# PW1555.net
KiCad netlist of a schematic drawn in Altium Designer
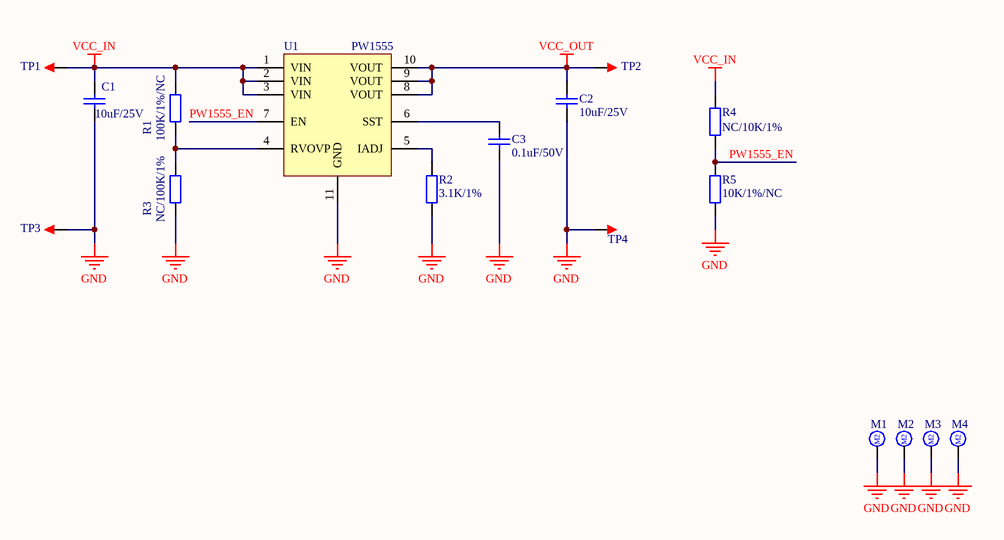
[diagram p0: PW1555.SchDoc]

(export (version "E")
  (design (tool "Eeschema 10.0.6"))
  (components
    (comp (ref "C1")
      (value "10uF/25V")
      (footprint "C0805_L")
      (description "贴片电容")
      (libsource (lib "0.1 - 电阻-电容-电感-晶振-晶体-磁珠-电位器") (part "C"))
    )
    (comp (ref "C2")
      (value "10uF/25V")
      (footprint "C0805_L")
      (description "贴片电容")
      (libsource (lib "0.1 - 电阻-电容-电感-晶振-晶体-磁珠-电位器") (part "C"))
    )
    (comp (ref "C3")
      (value "0.1uF/50V")
      (footprint "C0402_L")
      (description "贴片电容")
      (libsource (lib "0.1 - 电阻-电容-电感-晶振-晶体-磁珠-电位器") (part "C"))
    )
    (comp (ref "M1")
      (value "M2")
      (footprint "M2焊盘")
      (description "M2孔支撑柱")
      (libsource (lib "USER_Lib") (part "M2系列"))
    )
    (comp (ref "M2")
      (value "M2")
      (footprint "M2焊盘")
      (description "M2孔支撑柱")
      (libsource (lib "USER_Lib") (part "M2系列"))
    )
    (comp (ref "M3")
      (value "M2")
      (footprint "M2焊盘")
      (description "M2孔支撑柱")
      (libsource (lib "USER_Lib") (part "M2系列"))
    )
    (comp (ref "M4")
      (value "M2")
      (footprint "M2焊盘")
      (description "M2孔支撑柱")
      (libsource (lib "USER_Lib") (part "M2系列"))
    )
    (comp (ref "R1")
      (value "100K/1%/NC")
      (footprint "R0402_L")
      (description "贴片电阻")
      (libsource (lib "0.1 - 电阻-电容-电感-晶振-晶体-磁珠-电位器") (part "R"))
    )
    (comp (ref "R2")
      (value "3.1K/1%")
      (footprint "R0402_L")
      (description "贴片电阻")
      (libsource (lib "0.1 - 电阻-电容-电感-晶振-晶体-磁珠-电位器") (part "R"))
    )
    (comp (ref "R3")
      (value "NC/100K/1%")
      (footprint "R0402_L")
      (description "贴片电阻")
      (libsource (lib "0.1 - 电阻-电容-电感-晶振-晶体-磁珠-电位器") (part "R"))
    )
    (comp (ref "R4")
      (value "NC/10K/1%")
      (footprint "R0402_L")
      (description "贴片电阻")
      (libsource (lib "0.1 - 电阻-电容-电感-晶振-晶体-磁珠-电位器") (part "R"))
    )
    (comp (ref "R5")
      (value "10K/1%/NC")
      (footprint "R0402_L")
      (description "贴片电阻")
      (libsource (lib "0.1 - 电阻-电容-电感-晶振-晶体-磁珠-电位器") (part "R"))
    )
    (comp (ref "TP1")
      (value "TEST")
      (footprint "PAD_5x5")
      (description "测试点")
      (libsource (lib "0.5 - 按键-开关-蜂鸣器-保险丝-电池-测试点-Mark点") (part "TEST"))
    )
    (comp (ref "TP2")
      (value "TEST")
      (footprint "PAD_5x5")
      (description "测试点")
      (libsource (lib "0.5 - 按键-开关-蜂鸣器-保险丝-电池-测试点-Mark点") (part "TEST"))
    )
    (comp (ref "TP3")
      (value "TEST")
      (footprint "PAD_5x5")
      (description "测试点")
      (libsource (lib "0.5 - 按键-开关-蜂鸣器-保险丝-电池-测试点-Mark点") (part "TEST"))
    )
    (comp (ref "TP4")
      (value "TEST")
      (footprint "PAD_5x5")
      (description "测试点")
      (libsource (lib "0.5 - 按键-开关-蜂鸣器-保险丝-电池-测试点-Mark点") (part "TEST"))
    )
    (comp (ref "U1")
      (value "PW1555")
      (footprint "DFN3x3-10")
      (description "VOVP  ILIM保护芯片")
      (libsource (lib "USER_Lib") (part "PW1555"))
    )
  )
  (nets
    (net (code "1") (name "/PW1555_EN") (class "Default")
      (node (ref "R4") (pin "1") (pinfunction "1_1") (pintype "passive"))
      (node (ref "R5") (pin "2") (pinfunction "2_2") (pintype "passive"))
      (node (ref "U1") (pin "7") (pinfunction "EN_7") (pintype "passive"))
    )
    (net (code "2") (name "GND") (class "Default")
      (node (ref "C1") (pin "1") (pinfunction "1_1") (pintype "passive"))
      (node (ref "C2") (pin "1") (pinfunction "1_1") (pintype "passive"))
      (node (ref "C3") (pin "1") (pinfunction "1_1") (pintype "passive"))
      (node (ref "M1") (pin "1") (pinfunction "1_1") (pintype "passive"))
      (node (ref "M2") (pin "1") (pinfunction "1_1") (pintype "passive"))
      (node (ref "M3") (pin "1") (pinfunction "1_1") (pintype "passive"))
      (node (ref "M4") (pin "1") (pinfunction "1_1") (pintype "passive"))
      (node (ref "R2") (pin "1") (pinfunction "1_1") (pintype "passive"))
      (node (ref "R3") (pin "1") (pinfunction "1_1") (pintype "passive"))
      (node (ref "R5") (pin "1") (pinfunction "1_1") (pintype "passive"))
      (node (ref "TP3") (pin "1") (pinfunction "1_1") (pintype "passive"))
      (node (ref "TP4") (pin "1") (pinfunction "1_1") (pintype "passive"))
      (node (ref "U1") (pin "11") (pinfunction "GND_11") (pintype "passive"))
    )
    (net (code "3") (name "Net-(U1-IADJ)") (class "Default")
      (node (ref "R2") (pin "2") (pinfunction "2_2") (pintype "passive"))
      (node (ref "U1") (pin "5") (pinfunction "IADJ_5") (pintype "passive"))
    )
    (net (code "4") (name "Net-(U1-RVOVP)") (class "Default")
      (node (ref "R1") (pin "1") (pinfunction "1_1") (pintype "passive"))
      (node (ref "R3") (pin "2") (pinfunction "2_2") (pintype "passive"))
      (node (ref "U1") (pin "4") (pinfunction "RVOVP_4") (pintype "passive"))
    )
    (net (code "5") (name "Net-(U1-SST)") (class "Default")
      (node (ref "C3") (pin "2") (pinfunction "2_2") (pintype "passive"))
      (node (ref "U1") (pin "6") (pinfunction "SST_6") (pintype "passive"))
    )
    (net (code "6") (name "VCC_IN") (class "Default")
      (node (ref "C1") (pin "2") (pinfunction "2_2") (pintype "passive"))
      (node (ref "R1") (pin "2") (pinfunction "2_2") (pintype "passive"))
      (node (ref "R4") (pin "2") (pinfunction "2_2") (pintype "passive"))
      (node (ref "TP1") (pin "1") (pinfunction "1_1") (pintype "passive"))
      (node (ref "U1") (pin "1") (pinfunction "VIN_1") (pintype "passive"))
      (node (ref "U1") (pin "2") (pinfunction "VIN_2") (pintype "passive"))
      (node (ref "U1") (pin "3") (pinfunction "VIN_3") (pintype "passive"))
    )
    (net (code "7") (name "VCC_OUT") (class "Default")
      (node (ref "C2") (pin "2") (pinfunction "2_2") (pintype "passive"))
      (node (ref "TP2") (pin "1") (pinfunction "1_1") (pintype "passive"))
      (node (ref "U1") (pin "10") (pinfunction "VOUT_10") (pintype "passive"))
      (node (ref "U1") (pin "8") (pinfunction "VOUT_8") (pintype "passive"))
      (node (ref "U1") (pin "9") (pinfunction "VOUT_9") (pintype "passive"))
    )
  )
)
